# UD27C.net
KiCad netlist of a schematic drawn in EAGLE
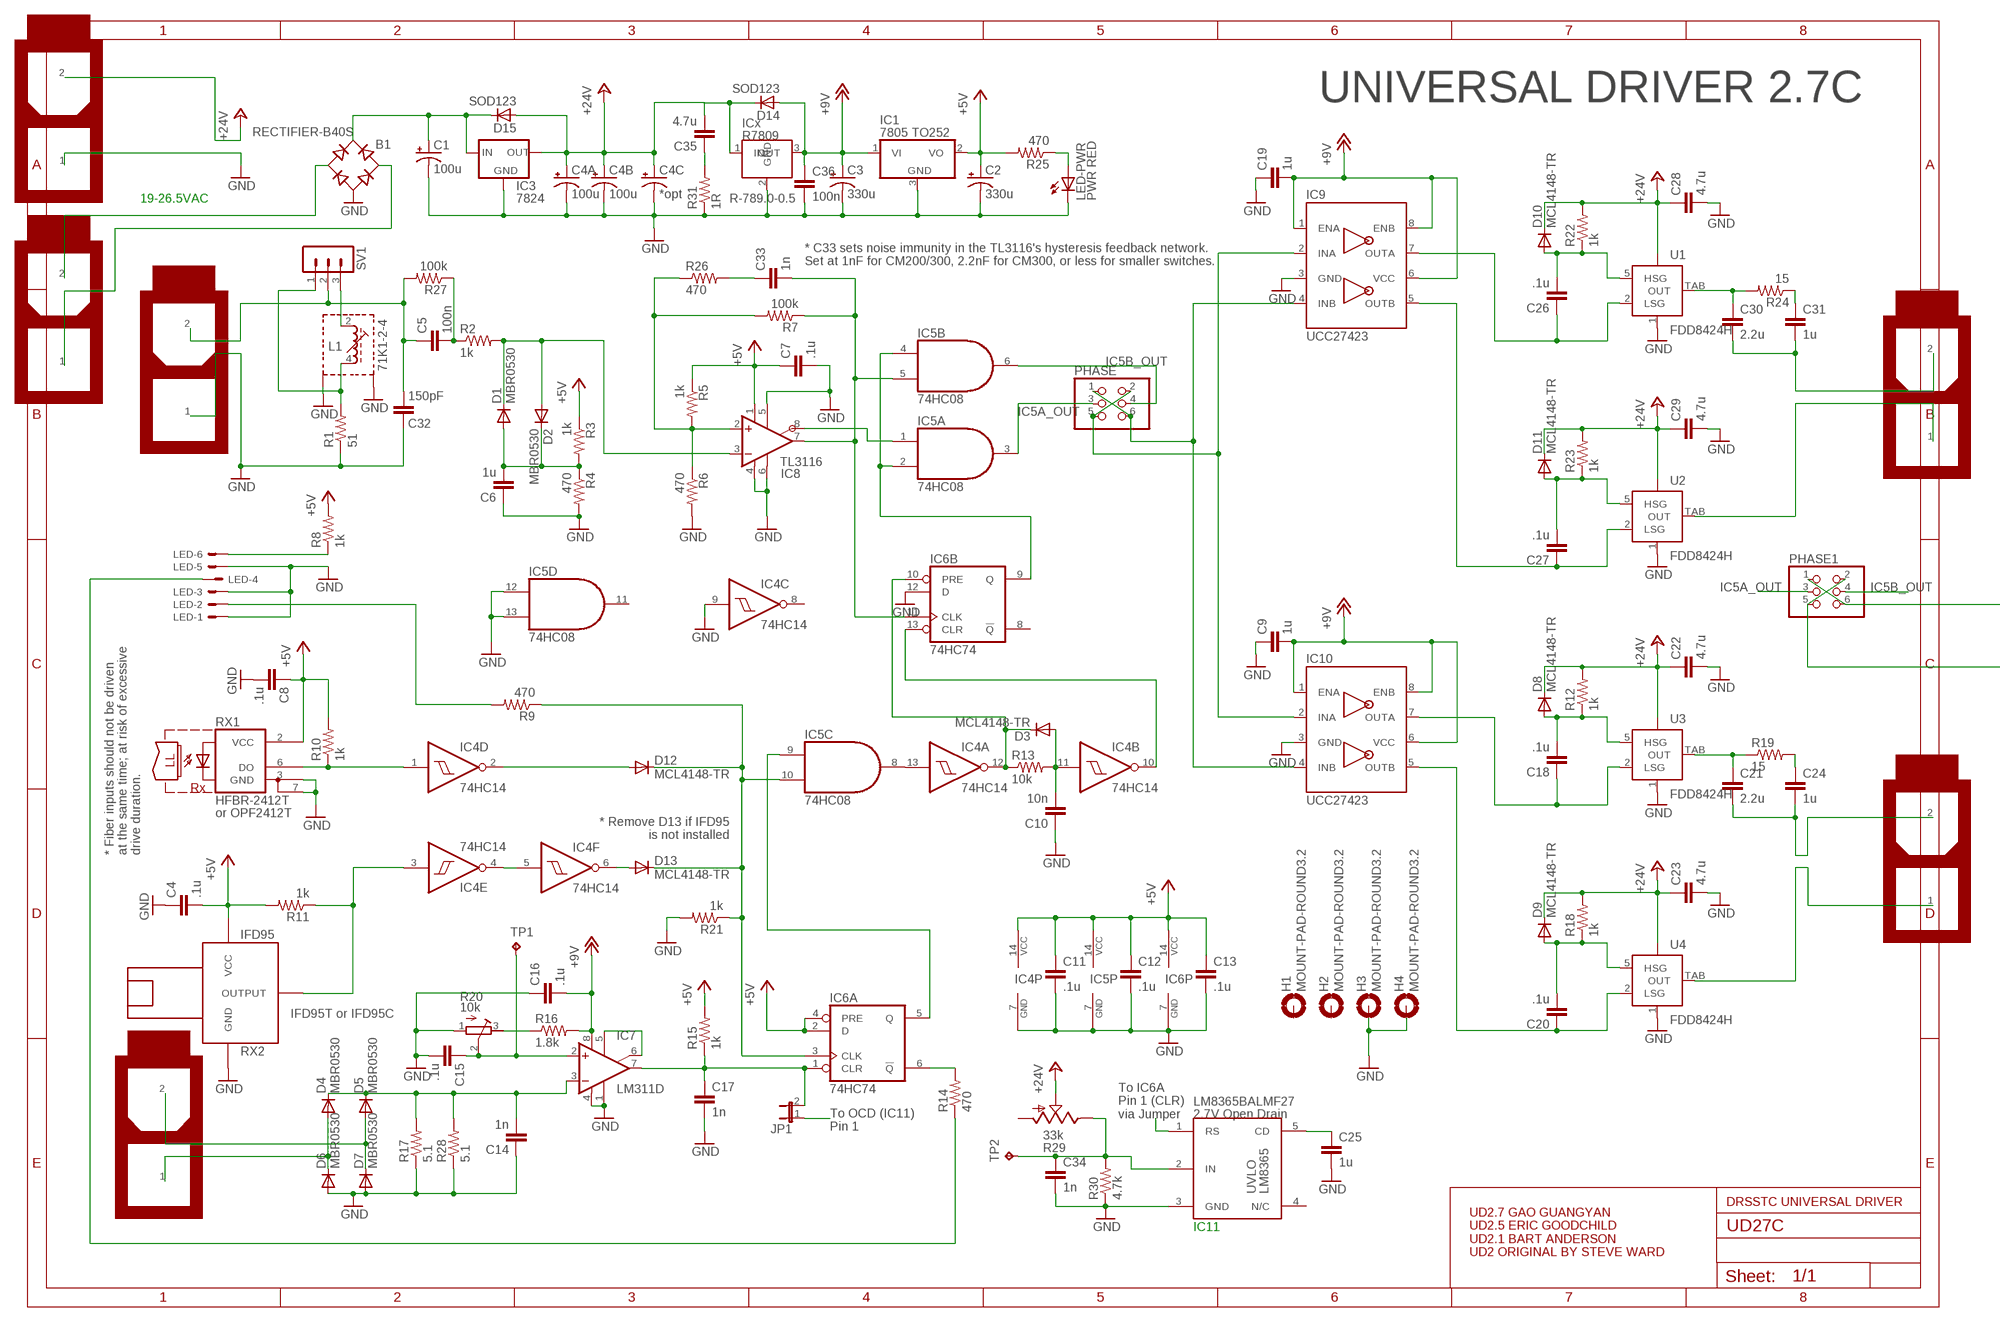
[diagram p0: schematic, sheet 1, part 1 of 2]
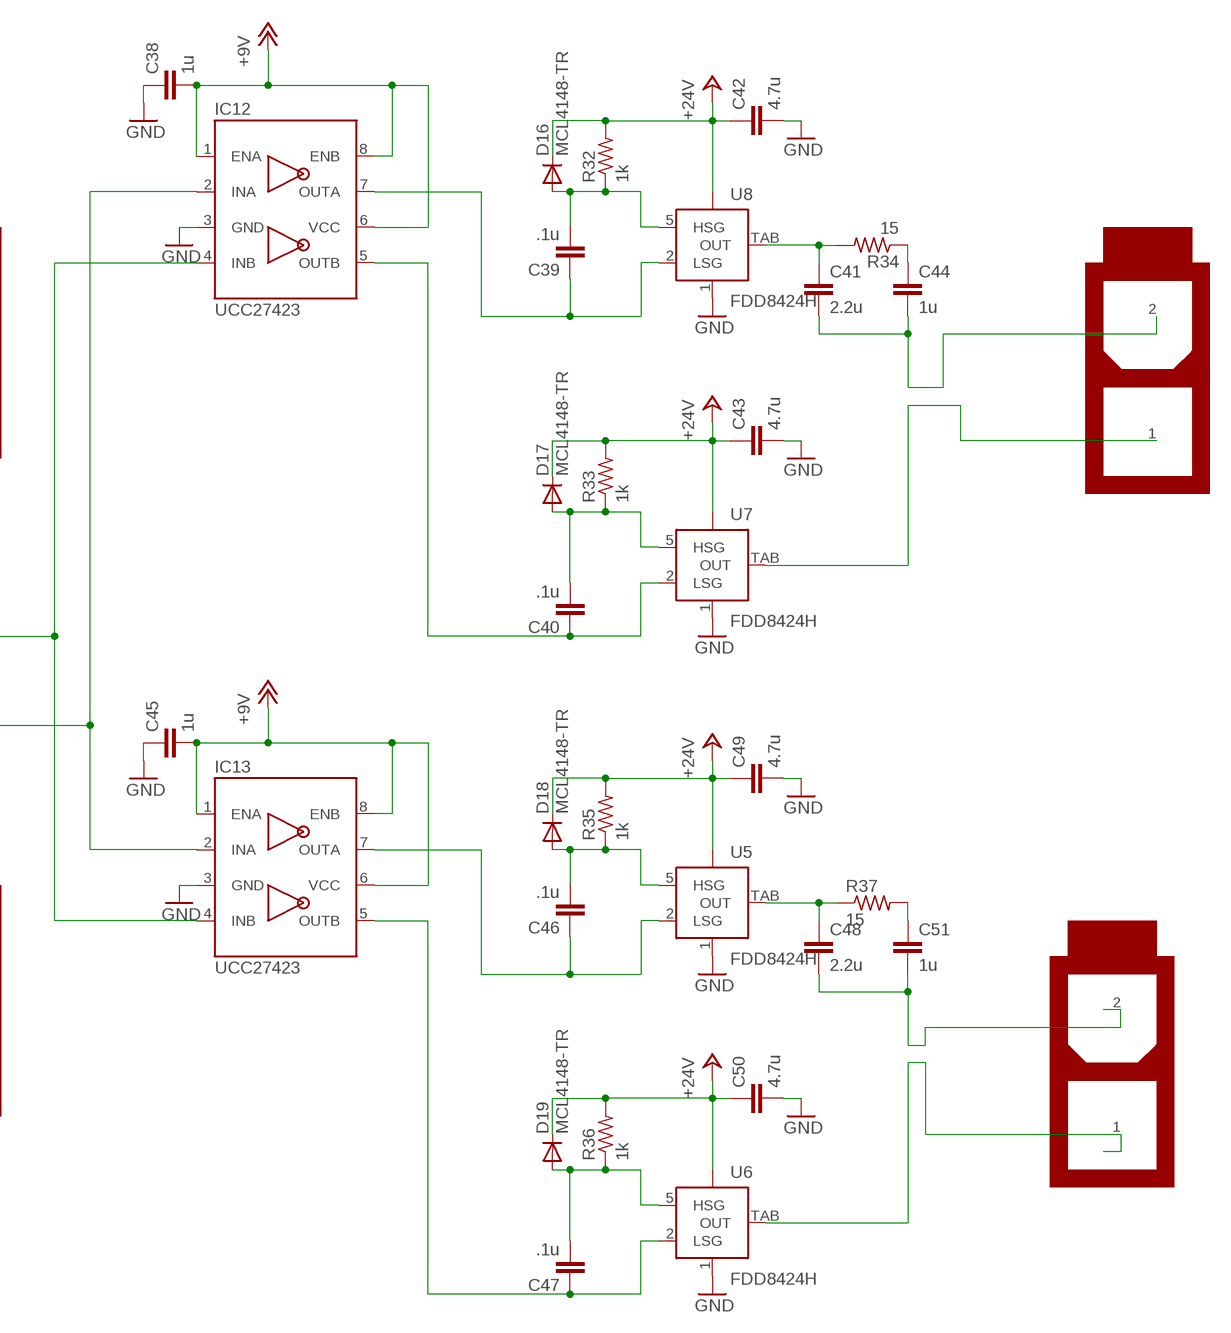
[diagram p1: schematic, sheet 1, part 2 of 2]

(export (version "E")
  (design (tool "Eeschema 10.0.6"))
  (components
    (comp (ref "B1")
      (value "RECTIFIER-B40S")
      (footprint "eagle-import:B40S")
      (libsource (lib "eagle-import") (part "RECTIFIER-B40S"))
    )
    (comp (ref "C1")
      (value "100u")
      (footprint "eagle-import:E3,5-8")
      (libsource (lib "eagle-import") (part "CPOL-USE3.5-8"))
    )
    (comp (ref "C2")
      (value "330u")
      (footprint "eagle-import:E3,5-8")
      (libsource (lib "eagle-import") (part "CPOL-USE3.5-8"))
    )
    (comp (ref "C3")
      (value "330u")
      (footprint "eagle-import:E3,5-8")
      (libsource (lib "eagle-import") (part "CPOL-USE3.5-8"))
    )
    (comp (ref "C4")
      (value ".1u")
      (footprint "eagle-import:C0805")
      (libsource (lib "eagle-import") (part "C-EUC0805"))
    )
    (comp (ref "C4A")
      (value "100u")
      (footprint "eagle-import:E3,5-8")
      (libsource (lib "eagle-import") (part "CPOL-USE3.5-8"))
    )
    (comp (ref "C4B")
      (value "100u")
      (footprint "eagle-import:E3,5-8")
      (libsource (lib "eagle-import") (part "CPOL-USE3.5-8"))
    )
    (comp (ref "C4C")
      (value "*opt")
      (footprint "eagle-import:E3,5-8")
      (libsource (lib "eagle-import") (part "CPOL-USE3.5-8"))
    )
    (comp (ref "C5")
      (value "100n")
      (footprint "eagle-import:C0805")
      (libsource (lib "eagle-import") (part "C-EUC0805"))
    )
    (comp (ref "C6")
      (value "1u")
      (footprint "eagle-import:C0805")
      (libsource (lib "eagle-import") (part "C-EUC0805"))
    )
    (comp (ref "C7")
      (value ".1u")
      (footprint "eagle-import:C0805")
      (libsource (lib "eagle-import") (part "C-EUC0805"))
    )
    (comp (ref "C8")
      (value ".1u")
      (footprint "eagle-import:C0805")
      (libsource (lib "eagle-import") (part "C-EUC0805"))
    )
    (comp (ref "C9")
      (value "1u")
      (footprint "eagle-import:C0805")
      (libsource (lib "eagle-import") (part "C-EUC0805"))
    )
    (comp (ref "C10")
      (value "10n")
      (footprint "eagle-import:C0805")
      (libsource (lib "eagle-import") (part "C-EUC0805"))
    )
    (comp (ref "C11")
      (value ".1u")
      (footprint "eagle-import:C0805")
      (libsource (lib "eagle-import") (part "C-EUC0805"))
    )
    (comp (ref "C12")
      (value ".1u")
      (footprint "eagle-import:C0805")
      (libsource (lib "eagle-import") (part "C-EUC0805"))
    )
    (comp (ref "C13")
      (value ".1u")
      (footprint "eagle-import:C0805")
      (libsource (lib "eagle-import") (part "C-EUC0805"))
    )
    (comp (ref "C14")
      (value "1n")
      (footprint "eagle-import:C0805")
      (libsource (lib "eagle-import") (part "C-EUC0805"))
    )
    (comp (ref "C15")
      (value ".1u")
      (footprint "eagle-import:C0805")
      (libsource (lib "eagle-import") (part "C-EUC0805"))
    )
    (comp (ref "C16")
      (value ".1u")
      (footprint "eagle-import:C0805")
      (libsource (lib "eagle-import") (part "C-EUC0805"))
    )
    (comp (ref "C17")
      (value "1n")
      (footprint "eagle-import:C0805")
      (libsource (lib "eagle-import") (part "C-EUC0805"))
    )
    (comp (ref "C18")
      (value ".1u")
      (footprint "eagle-import:C0805")
      (libsource (lib "eagle-import") (part "C-EUC0805"))
    )
    (comp (ref "C19")
      (value "1u")
      (footprint "eagle-import:C0805")
      (libsource (lib "eagle-import") (part "C-EUC0805"))
    )
    (comp (ref "C20")
      (value ".1u")
      (footprint "eagle-import:C0805")
      (libsource (lib "eagle-import") (part "C-EUC0805"))
    )
    (comp (ref "C21")
      (value "2.2u")
      (footprint "eagle-import:C1210")
      (libsource (lib "eagle-import") (part "C-EUC1210"))
    )
    (comp (ref "C22")
      (value "4.7u")
      (footprint "eagle-import:C1206")
      (libsource (lib "eagle-import") (part "C-EUC1206"))
    )
    (comp (ref "C23")
      (value "4.7u")
      (footprint "eagle-import:C1206")
      (libsource (lib "eagle-import") (part "C-EUC1206"))
    )
    (comp (ref "C24")
      (value "1u")
      (footprint "eagle-import:C1206")
      (libsource (lib "eagle-import") (part "C-EUC1206"))
    )
    (comp (ref "C25")
      (value "1u")
      (footprint "eagle-import:C0805")
      (libsource (lib "eagle-import") (part "C-EUC0805"))
    )
    (comp (ref "C26")
      (value ".1u")
      (footprint "eagle-import:C0805")
      (libsource (lib "eagle-import") (part "C-EUC0805"))
    )
    (comp (ref "C27")
      (value ".1u")
      (footprint "eagle-import:C0805")
      (libsource (lib "eagle-import") (part "C-EUC0805"))
    )
    (comp (ref "C28")
      (value "4.7u")
      (footprint "eagle-import:C1206")
      (libsource (lib "eagle-import") (part "C-EUC1206"))
    )
    (comp (ref "C29")
      (value "4.7u")
      (footprint "eagle-import:C1206")
      (libsource (lib "eagle-import") (part "C-EUC1206"))
    )
    (comp (ref "C30")
      (value "2.2u")
      (footprint "eagle-import:C1210")
      (libsource (lib "eagle-import") (part "C-EUC1210"))
    )
    (comp (ref "C31")
      (value "1u")
      (footprint "eagle-import:C1206")
      (libsource (lib "eagle-import") (part "C-EUC1206"))
    )
    (comp (ref "C32")
      (value "150pF")
      (footprint "eagle-import:C0805")
      (libsource (lib "eagle-import") (part "C-EUC0805"))
    )
    (comp (ref "C33")
      (value "1n")
      (footprint "eagle-import:C1206")
      (libsource (lib "eagle-import") (part "C-EUC1206"))
    )
    (comp (ref "C34")
      (value "1n")
      (footprint "eagle-import:C0805")
      (libsource (lib "eagle-import") (part "C-EUC0805"))
    )
    (comp (ref "C35")
      (value "4.7u")
      (footprint "eagle-import:C1206K")
      (libsource (lib "eagle-import") (part "C-EUC1206K"))
    )
    (comp (ref "C36")
      (value "100n")
      (footprint "eagle-import:C0805")
      (libsource (lib "eagle-import") (part "C-EUC0805"))
    )
    (comp (ref "C38")
      (value "1u")
      (footprint "eagle-import:C0805")
      (libsource (lib "eagle-import") (part "C-EUC0805"))
    )
    (comp (ref "C39")
      (value ".1u")
      (footprint "eagle-import:C0805")
      (libsource (lib "eagle-import") (part "C-EUC0805"))
    )
    (comp (ref "C40")
      (value ".1u")
      (footprint "eagle-import:C0805")
      (libsource (lib "eagle-import") (part "C-EUC0805"))
    )
    (comp (ref "C41")
      (value "2.2u")
      (footprint "eagle-import:C1210")
      (libsource (lib "eagle-import") (part "C-EUC1210"))
    )
    (comp (ref "C42")
      (value "4.7u")
      (footprint "eagle-import:C1206")
      (libsource (lib "eagle-import") (part "C-EUC1206"))
    )
    (comp (ref "C43")
      (value "4.7u")
      (footprint "eagle-import:C1206")
      (libsource (lib "eagle-import") (part "C-EUC1206"))
    )
    (comp (ref "C44")
      (value "1u")
      (footprint "eagle-import:C1206")
      (libsource (lib "eagle-import") (part "C-EUC1206"))
    )
    (comp (ref "C45")
      (value "1u")
      (footprint "eagle-import:C0805")
      (libsource (lib "eagle-import") (part "C-EUC0805"))
    )
    (comp (ref "C46")
      (value ".1u")
      (footprint "eagle-import:C0805")
      (libsource (lib "eagle-import") (part "C-EUC0805"))
    )
    (comp (ref "C47")
      (value ".1u")
      (footprint "eagle-import:C0805")
      (libsource (lib "eagle-import") (part "C-EUC0805"))
    )
    (comp (ref "C48")
      (value "2.2u")
      (footprint "eagle-import:C1210")
      (libsource (lib "eagle-import") (part "C-EUC1210"))
    )
    (comp (ref "C49")
      (value "4.7u")
      (footprint "eagle-import:C1206")
      (libsource (lib "eagle-import") (part "C-EUC1206"))
    )
    (comp (ref "C50")
      (value "4.7u")
      (footprint "eagle-import:C1206")
      (libsource (lib "eagle-import") (part "C-EUC1206"))
    )
    (comp (ref "C51")
      (value "1u")
      (footprint "eagle-import:C1206")
      (libsource (lib "eagle-import") (part "C-EUC1206"))
    )
    (comp (ref "D1")
      (value "MBR0530")
      (footprint "eagle-import:SOD323-W")
      (libsource (lib "eagle-import") (part "1N4148"))
    )
    (comp (ref "D2")
      (value "MBR0530")
      (footprint "eagle-import:SOD323-W")
      (libsource (lib "eagle-import") (part "1N4148"))
    )
    (comp (ref "D3")
      (value "MCL4148-TR")
      (footprint "eagle-import:SOD323-W")
      (libsource (lib "eagle-import") (part "1N4148"))
    )
    (comp (ref "D4")
      (value "MBR0530")
      (footprint "eagle-import:SOD323-W")
      (libsource (lib "eagle-import") (part "1N4148"))
    )
    (comp (ref "D5")
      (value "MBR0530")
      (footprint "eagle-import:SOD323-W")
      (libsource (lib "eagle-import") (part "1N4148"))
    )
    (comp (ref "D6")
      (value "MBR0530")
      (footprint "eagle-import:SOD323-W")
      (libsource (lib "eagle-import") (part "1N4148"))
    )
    (comp (ref "D7")
      (value "MBR0530")
      (footprint "eagle-import:SOD323-W")
      (libsource (lib "eagle-import") (part "1N4148"))
    )
    (comp (ref "D8")
      (value "MCL4148-TR")
      (footprint "eagle-import:SOD323-W")
      (libsource (lib "eagle-import") (part "1N4148"))
    )
    (comp (ref "D9")
      (value "MCL4148-TR")
      (footprint "eagle-import:SOD323-W")
      (libsource (lib "eagle-import") (part "1N4148"))
    )
    (comp (ref "D10")
      (value "MCL4148-TR")
      (footprint "eagle-import:SOD323-W")
      (libsource (lib "eagle-import") (part "1N4148"))
    )
    (comp (ref "D11")
      (value "MCL4148-TR")
      (footprint "eagle-import:SOD323-W")
      (libsource (lib "eagle-import") (part "1N4148"))
    )
    (comp (ref "D12")
      (value "MCL4148-TR")
      (footprint "eagle-import:SOD323-W")
      (libsource (lib "eagle-import") (part "1N4148"))
    )
    (comp (ref "D13")
      (value "MCL4148-TR")
      (footprint "eagle-import:SOD323-W")
      (libsource (lib "eagle-import") (part "1N4148"))
    )
    (comp (ref "D14")
      (value "SOD123")
      (footprint "eagle-import:SOD123")
      (libsource (lib "eagle-import") (part "D-SOD123"))
    )
    (comp (ref "D15")
      (value "SOD123")
      (footprint "eagle-import:SOD123")
      (libsource (lib "eagle-import") (part "D-SOD123"))
    )
    (comp (ref "D16")
      (value "MCL4148-TR")
      (footprint "eagle-import:SOD323-W")
      (libsource (lib "eagle-import") (part "1N4148"))
    )
    (comp (ref "D17")
      (value "MCL4148-TR")
      (footprint "eagle-import:SOD323-W")
      (libsource (lib "eagle-import") (part "1N4148"))
    )
    (comp (ref "D18")
      (value "MCL4148-TR")
      (footprint "eagle-import:SOD323-W")
      (libsource (lib "eagle-import") (part "1N4148"))
    )
    (comp (ref "D19")
      (value "MCL4148-TR")
      (footprint "eagle-import:SOD323-W")
      (libsource (lib "eagle-import") (part "1N4148"))
    )
    (comp (ref "H1")
      (value "MOUNT-PAD-ROUND3.2")
      (footprint "eagle-import:3,2-PAD")
      (libsource (lib "eagle-import") (part "MOUNT-PAD-ROUND3.2"))
    )
    (comp (ref "H2")
      (value "MOUNT-PAD-ROUND3.2")
      (footprint "eagle-import:3,2-PAD")
      (libsource (lib "eagle-import") (part "MOUNT-PAD-ROUND3.2"))
    )
    (comp (ref "H3")
      (value "MOUNT-PAD-ROUND3.2")
      (footprint "eagle-import:3,2-PAD")
      (libsource (lib "eagle-import") (part "MOUNT-PAD-ROUND3.2"))
    )
    (comp (ref "H4")
      (value "MOUNT-PAD-ROUND3.2")
      (footprint "eagle-import:3,2-PAD")
      (libsource (lib "eagle-import") (part "MOUNT-PAD-ROUND3.2"))
    )
    (comp (ref "IC1")
      (value "7805 TO252")
      (footprint "eagle-import:TO252")
      (libsource (lib "eagle-import") (part "78DT05"))
    )
    (comp (ref "IC2")
      (value "R78XX")
      (footprint "eagle-import:TO220S")
      (libsource (lib "eagle-import") (part "R78XX"))
    )
    (comp (ref "IC3")
      (value "7824")
      (footprint "eagle-import:D2PACK")
      (libsource (lib "eagle-import") (part "78XXD2PAK"))
    )
    (comp (ref "IC4")
      (value "74HC14")
      (footprint "eagle-import:SO14")
      (libsource (lib "eagle-import") (part "7414D"))
    )
    (comp (ref "IC5")
      (value "74HC08")
      (footprint "eagle-import:SO14")
      (libsource (lib "eagle-import") (part "7408DALS"))
    )
    (comp (ref "IC6")
      (value "74HC74")
      (footprint "eagle-import:SO14")
      (libsource (lib "eagle-import") (part "7474DLS"))
    )
    (comp (ref "IC7")
      (value "LM311D")
      (footprint "eagle-import:SO08")
      (libsource (lib "eagle-import") (part "LM311D"))
    )
    (comp (ref "IC8")
      (value "TL3116")
      (footprint "eagle-import:SO08")
      (libsource (lib "eagle-import") (part "TL3116"))
    )
    (comp (ref "IC9")
      (value "UCC27423")
      (footprint "eagle-import:SO08")
      (libsource (lib "eagle-import") (part "UCC27423"))
    )
    (comp (ref "IC10")
      (value "UCC27423")
      (footprint "eagle-import:SO08")
      (libsource (lib "eagle-import") (part "UCC27423"))
    )
    (comp (ref "IC11")
      (value "LM8365")
      (footprint "eagle-import:SOT25")
      (libsource (lib "eagle-import") (part "LM8365"))
    )
    (comp (ref "IC12")
      (value "UCC27423")
      (footprint "eagle-import:SO08")
      (libsource (lib "eagle-import") (part "UCC27423"))
    )
    (comp (ref "IC13")
      (value "UCC27423")
      (footprint "eagle-import:SO08")
      (libsource (lib "eagle-import") (part "UCC27423"))
    )
    (comp (ref "JP1")
      (value "JP1E")
      (footprint "eagle-import:JP1")
      (libsource (lib "eagle-import") (part "JP1E"))
    )
    (comp (ref "L1")
      (value "71K1-2-4")
      (footprint "eagle-import:71K")
      (libsource (lib "eagle-import") (part "71K1-2-4"))
    )
    (comp (ref "LED")
      (value "22-23-2061")
      (footprint "eagle-import:22-23-2061")
      (fields (field (name "MF") "MOLEX"))
      (libsource (lib "eagle-import") (part "22-23-2061"))
    )
    (comp (ref "LED-PWR")
      (value "PWR RED")
      (footprint "eagle-import:CHIP-LED0805")
      (libsource (lib "eagle-import") (part "LEDCHIP-LED0805"))
    )
    (comp (ref "PHASE")
      (value "PINHD-2X3")
      (footprint "eagle-import:2X03")
      (libsource (lib "eagle-import") (part "PINHD-2X3"))
    )
    (comp (ref "PHASE1")
      (value "PINHD-2X3")
      (footprint "eagle-import:2X03")
      (libsource (lib "eagle-import") (part "PINHD-2X3"))
    )
    (comp (ref "R1")
      (value "51")
      (footprint "eagle-import:0411_15")
      (libsource (lib "eagle-import") (part "R-US_0411/15"))
    )
    (comp (ref "R2")
      (value "1k")
      (footprint "eagle-import:M0805")
      (libsource (lib "eagle-import") (part "R-US_M0805"))
    )
    (comp (ref "R3")
      (value "1k")
      (footprint "eagle-import:M0805")
      (libsource (lib "eagle-import") (part "R-US_M0805"))
    )
    (comp (ref "R4")
      (value "470")
      (footprint "eagle-import:M0805")
      (libsource (lib "eagle-import") (part "R-US_M0805"))
    )
    (comp (ref "R5")
      (value "1k")
      (footprint "eagle-import:M0805")
      (libsource (lib "eagle-import") (part "R-US_M0805"))
    )
    (comp (ref "R6")
      (value "470")
      (footprint "eagle-import:M0805")
      (libsource (lib "eagle-import") (part "R-US_M0805"))
    )
    (comp (ref "R7")
      (value "100k")
      (footprint "eagle-import:M0805")
      (libsource (lib "eagle-import") (part "R-US_M0805"))
    )
    (comp (ref "R8")
      (value "1k")
      (footprint "eagle-import:R0805")
      (libsource (lib "eagle-import") (part "R-US_R0805"))
    )
    (comp (ref "R9")
      (value "470")
      (footprint "eagle-import:R0805")
      (libsource (lib "eagle-import") (part "R-US_R0805"))
    )
    (comp (ref "R10")
      (value "1k")
      (footprint "eagle-import:R0805")
      (libsource (lib "eagle-import") (part "R-US_R0805"))
    )
    (comp (ref "R11")
      (value "1k")
      (footprint "eagle-import:R0805")
      (libsource (lib "eagle-import") (part "R-US_R0805"))
    )
    (comp (ref "R12")
      (value "1k")
      (footprint "eagle-import:M0805")
      (libsource (lib "eagle-import") (part "R-US_M0805"))
    )
    (comp (ref "R13")
      (value "10k")
      (footprint "eagle-import:R0805")
      (libsource (lib "eagle-import") (part "R-US_R0805"))
    )
    (comp (ref "R14")
      (value "470")
      (footprint "eagle-import:R0805")
      (libsource (lib "eagle-import") (part "R-US_R0805"))
    )
    (comp (ref "R15")
      (value "1k")
      (footprint "eagle-import:R0805")
      (libsource (lib "eagle-import") (part "R-US_R0805"))
    )
    (comp (ref "R16")
      (value "1.8k")
      (footprint "eagle-import:R0805")
      (libsource (lib "eagle-import") (part "R-US_R0805"))
    )
    (comp (ref "R17")
      (value "5.1")
      (footprint "eagle-import:0309_12")
      (libsource (lib "eagle-import") (part "R-US_0309/12"))
    )
    (comp (ref "R18")
      (value "1k")
      (footprint "eagle-import:R0805")
      (libsource (lib "eagle-import") (part "R-US_R0805"))
    )
    (comp (ref "R19")
      (value "15")
      (footprint "eagle-import:R1210W")
      (libsource (lib "eagle-import") (part "R-US_R1210W"))
    )
    (comp (ref "R20")
      (value "10k")
      (footprint "eagle-import:RTRIM3296W")
      (libsource (lib "eagle-import") (part "R-TRIMM3296W"))
    )
    (comp (ref "R21")
      (value "1k")
      (footprint "eagle-import:R0805")
      (libsource (lib "eagle-import") (part "R-US_R0805"))
    )
    (comp (ref "R22")
      (value "1k")
      (footprint "eagle-import:M0805")
      (libsource (lib "eagle-import") (part "R-US_M0805"))
    )
    (comp (ref "R23")
      (value "1k")
      (footprint "eagle-import:R0805")
      (libsource (lib "eagle-import") (part "R-US_R0805"))
    )
    (comp (ref "R24")
      (value "15")
      (footprint "eagle-import:R1210W")
      (libsource (lib "eagle-import") (part "R-US_R1210W"))
    )
    (comp (ref "R25")
      (value "470")
      (footprint "eagle-import:M0805")
      (libsource (lib "eagle-import") (part "R-US_M0805"))
    )
    (comp (ref "R26")
      (value "470")
      (footprint "eagle-import:M0805")
      (libsource (lib "eagle-import") (part "R-US_M0805"))
    )
    (comp (ref "R27")
      (value "100k")
      (footprint "eagle-import:M0805")
      (libsource (lib "eagle-import") (part "R-US_M0805"))
    )
    (comp (ref "R28")
      (value "5.1")
      (footprint "eagle-import:0309_12")
      (libsource (lib "eagle-import") (part "R-US_0309/12"))
    )
    (comp (ref "R29")
      (value "33k")
      (footprint "eagle-import:3223J")
      (libsource (lib "eagle-import") (part "TRIM_US-3223J"))
    )
    (comp (ref "R30")
      (value "4.7k")
      (footprint "eagle-import:R0805")
      (libsource (lib "eagle-import") (part "R-US_R0805"))
    )
    (comp (ref "R31")
      (value "1R")
      (footprint "eagle-import:M0805")
      (libsource (lib "eagle-import") (part "R-US_M0805"))
    )
    (comp (ref "R32")
      (value "1k")
      (footprint "eagle-import:M0805")
      (libsource (lib "eagle-import") (part "R-US_M0805"))
    )
    (comp (ref "R33")
      (value "1k")
      (footprint "eagle-import:R0805")
      (libsource (lib "eagle-import") (part "R-US_R0805"))
    )
    (comp (ref "R34")
      (value "15")
      (footprint "eagle-import:R1210W")
      (libsource (lib "eagle-import") (part "R-US_R1210W"))
    )
    (comp (ref "R35")
      (value "1k")
      (footprint "eagle-import:M0805")
      (libsource (lib "eagle-import") (part "R-US_M0805"))
    )
    (comp (ref "R36")
      (value "1k")
      (footprint "eagle-import:R0805")
      (libsource (lib "eagle-import") (part "R-US_R0805"))
    )
    (comp (ref "R37")
      (value "15")
      (footprint "eagle-import:R1210W")
      (libsource (lib "eagle-import") (part "R-US_R1210W"))
    )
    (comp (ref "RX1")
      (value "HFBR-2412T")
      (footprint "eagle-import:HFBR-X41XT")
      (fields (field (name "MF") "AGILENT TECHNOLOGIES"))
      (libsource (lib "eagle-import") (part "HFBR-2412T"))
    )
    (comp (ref "RX2")
      (value "IFD95")
      (footprint "eagle-import:OPTO-RECEIVER")
      (libsource (lib "eagle-import") (part "IFD95"))
    )
    (comp (ref "SV1")
      (value "MA03-1")
      (footprint "eagle-import:MA03-1")
      (libsource (lib "eagle-import") (part "MA03-1"))
    )
    (comp (ref "TP1")
      (value "TPTP16R")
      (footprint "eagle-import:TP16R")
      (libsource (lib "eagle-import") (part "TPTP16R"))
    )
    (comp (ref "TP2")
      (value "TPB1,27")
      (footprint "eagle-import:B1,27")
      (libsource (lib "eagle-import") (part "TPB1,27"))
    )
    (comp (ref "U$1")
      (value "5566-2NP")
      (footprint "eagle-import:5566-2NP")
      (libsource (lib "eagle-import") (part "5566-2NP"))
    )
    (comp (ref "U$2")
      (value "5566-2NP")
      (footprint "eagle-import:5566-2NP")
      (libsource (lib "eagle-import") (part "5566-2NP"))
    )
    (comp (ref "U$3")
      (value "5566-2NP")
      (footprint "eagle-import:5566-2NP")
      (libsource (lib "eagle-import") (part "5566-2NP"))
    )
    (comp (ref "U$4")
      (value "5566-2NP")
      (footprint "eagle-import:5566-2NP")
      (libsource (lib "eagle-import") (part "5566-2NP"))
    )
    (comp (ref "U$5")
      (value "5566-2NP")
      (footprint "eagle-import:5566-2NP")
      (libsource (lib "eagle-import") (part "5566-2NP"))
    )
    (comp (ref "U$6")
      (value "5566-2NP")
      (footprint "eagle-import:5566-2NP")
      (libsource (lib "eagle-import") (part "5566-2NP"))
    )
    (comp (ref "U$7")
      (value "5566-2NP")
      (footprint "eagle-import:5566-2NP")
      (libsource (lib "eagle-import") (part "5566-2NP"))
    )
    (comp (ref "U$8")
      (value "5566-2NP")
      (footprint "eagle-import:5566-2NP")
      (libsource (lib "eagle-import") (part "5566-2NP"))
    )
    (comp (ref "U1")
      (value "FDD8424H")
      (footprint "eagle-import:GGY_TO252_5")
      (libsource (lib "eagle-import") (part "GGY_FDD8424H"))
    )
    (comp (ref "U2")
      (value "FDD8424H")
      (footprint "eagle-import:GGY_TO252_5")
      (libsource (lib "eagle-import") (part "GGY_FDD8424H"))
    )
    (comp (ref "U3")
      (value "FDD8424H")
      (footprint "eagle-import:GGY_TO252_5")
      (libsource (lib "eagle-import") (part "GGY_FDD8424H"))
    )
    (comp (ref "U4")
      (value "FDD8424H")
      (footprint "eagle-import:GGY_TO252_5")
      (libsource (lib "eagle-import") (part "GGY_FDD8424H"))
    )
    (comp (ref "U5")
      (value "FDD8424H")
      (footprint "eagle-import:GGY_TO252_5")
      (libsource (lib "eagle-import") (part "GGY_FDD8424H"))
    )
    (comp (ref "U6")
      (value "FDD8424H")
      (footprint "eagle-import:GGY_TO252_5")
      (libsource (lib "eagle-import") (part "GGY_FDD8424H"))
    )
    (comp (ref "U7")
      (value "FDD8424H")
      (footprint "eagle-import:GGY_TO252_5")
      (libsource (lib "eagle-import") (part "GGY_FDD8424H"))
    )
    (comp (ref "U8")
      (value "FDD8424H")
      (footprint "eagle-import:GGY_TO252_5")
      (libsource (lib "eagle-import") (part "GGY_FDD8424H"))
    )
  )
  (nets
    (net (code "1") (name "+5V") (class "Default")
      (node (ref "C11") (pin "1") (pinfunction "1_1") (pintype "passive"))
      (node (ref "C12") (pin "1") (pinfunction "1_1") (pintype "passive"))
      (node (ref "C13") (pin "1") (pinfunction "1_1") (pintype "passive"))
      (node (ref "C2") (pin "+") (pinfunction "+_+") (pintype "passive"))
      (node (ref "C4") (pin "2") (pinfunction "2_2") (pintype "passive"))
      (node (ref "C7") (pin "1") (pinfunction "1_1") (pintype "passive"))
      (node (ref "C8") (pin "1") (pinfunction "1_1") (pintype "passive"))
      (node (ref "IC1") (pin "2") (pinfunction "VO_2") (pintype "passive"))
      (node (ref "IC4") (pin "14") (pinfunction "VCC_14") (pintype "power_in"))
      (node (ref "IC5") (pin "14") (pinfunction "VCC_14") (pintype "power_in"))
      (node (ref "IC6") (pin "14") (pinfunction "VCC_14") (pintype "power_in"))
      (node (ref "IC6") (pin "2") (pinfunction "D_2") (pintype "input"))
      (node (ref "IC6") (pin "4") (pinfunction "PRE_4") (pintype "input"))
      (node (ref "IC8") (pin "1") (pinfunction "V+_1") (pintype "power_in"))
      (node (ref "R10") (pin "2") (pinfunction "2_2") (pintype "passive"))
      (node (ref "R11") (pin "2") (pinfunction "2_2") (pintype "passive"))
      (node (ref "R15") (pin "2") (pinfunction "2_2") (pintype "passive"))
      (node (ref "R25") (pin "2") (pinfunction "2_2") (pintype "passive"))
      (node (ref "R3") (pin "1") (pinfunction "1_1") (pintype "passive"))
      (node (ref "R5") (pin "1") (pinfunction "1_1") (pintype "passive"))
      (node (ref "R8") (pin "2") (pinfunction "2_2") (pintype "passive"))
      (node (ref "RX1") (pin "2") (pinfunction "VCC_2") (pintype "power_in"))
      (node (ref "RX2") (pin "P$3") (pinfunction "VCC_P$3") (pintype "bidirectional"))
    )
    (net (code "2") (name "+9V") (class "Default")
      (node (ref "C16") (pin "2") (pinfunction "2_2") (pintype "passive"))
      (node (ref "C19") (pin "2") (pinfunction "2_2") (pintype "passive"))
      (node (ref "C3") (pin "+") (pinfunction "+_+") (pintype "passive"))
      (node (ref "C36") (pin "1") (pinfunction "1_1") (pintype "passive"))
      (node (ref "C38") (pin "2") (pinfunction "2_2") (pintype "passive"))
      (node (ref "C45") (pin "2") (pinfunction "2_2") (pintype "passive"))
      (node (ref "C9") (pin "2") (pinfunction "2_2") (pintype "passive"))
      (node (ref "D14") (pin "2") (pinfunction "A_2") (pintype "passive"))
      (node (ref "IC1") (pin "1") (pinfunction "VI_1") (pintype "input"))
      (node (ref "IC10") (pin "1") (pinfunction "ENA_1") (pintype "bidirectional"))
      (node (ref "IC10") (pin "6") (pinfunction "VCC_6") (pintype "bidirectional"))
      (node (ref "IC10") (pin "8") (pinfunction "ENB_8") (pintype "bidirectional"))
      (node (ref "IC12") (pin "1") (pinfunction "ENA_1") (pintype "bidirectional"))
      (node (ref "IC12") (pin "6") (pinfunction "VCC_6") (pintype "bidirectional"))
      (node (ref "IC12") (pin "8") (pinfunction "ENB_8") (pintype "bidirectional"))
      (node (ref "IC13") (pin "1") (pinfunction "ENA_1") (pintype "bidirectional"))
      (node (ref "IC13") (pin "6") (pinfunction "VCC_6") (pintype "bidirectional"))
      (node (ref "IC13") (pin "8") (pinfunction "ENB_8") (pintype "bidirectional"))
      (node (ref "IC2") (pin "3") (pinfunction "OUT_3") (pintype "bidirectional"))
      (node (ref "IC7") (pin "8") (pinfunction "V+_8") (pintype "power_in"))
      (node (ref "IC9") (pin "1") (pinfunction "ENA_1") (pintype "bidirectional"))
      (node (ref "IC9") (pin "6") (pinfunction "VCC_6") (pintype "bidirectional"))
      (node (ref "IC9") (pin "8") (pinfunction "ENB_8") (pintype "bidirectional"))
      (node (ref "R16") (pin "2") (pinfunction "2_2") (pintype "passive"))
    )
    (net (code "3") (name "+24V") (class "Default")
      (node (ref "C22") (pin "1") (pinfunction "1_1") (pintype "passive"))
      (node (ref "C23") (pin "1") (pinfunction "1_1") (pintype "passive"))
      (node (ref "C28") (pin "1") (pinfunction "1_1") (pintype "passive"))
      (node (ref "C29") (pin "1") (pinfunction "1_1") (pintype "passive"))
      (node (ref "C35") (pin "2") (pinfunction "2_2") (pintype "passive"))
      (node (ref "C42") (pin "1") (pinfunction "1_1") (pintype "passive"))
      (node (ref "C43") (pin "1") (pinfunction "1_1") (pintype "passive"))
      (node (ref "C49") (pin "1") (pinfunction "1_1") (pintype "passive"))
      (node (ref "C4A") (pin "+") (pinfunction "+_+") (pintype "passive"))
      (node (ref "C4B") (pin "+") (pinfunction "+_+") (pintype "passive"))
      (node (ref "C4C") (pin "+") (pinfunction "+_+") (pintype "passive"))
      (node (ref "C50") (pin "1") (pinfunction "1_1") (pintype "passive"))
      (node (ref "D10") (pin "C") (pinfunction "C_C") (pintype "passive"))
      (node (ref "D11") (pin "C") (pinfunction "C_C") (pintype "passive"))
      (node (ref "D14") (pin "1") (pinfunction "C_1") (pintype "passive"))
      (node (ref "D15") (pin "2") (pinfunction "A_2") (pintype "passive"))
      (node (ref "D16") (pin "C") (pinfunction "C_C") (pintype "passive"))
      (node (ref "D17") (pin "C") (pinfunction "C_C") (pintype "passive"))
      (node (ref "D18") (pin "C") (pinfunction "C_C") (pintype "passive"))
      (node (ref "D19") (pin "C") (pinfunction "C_C") (pintype "passive"))
      (node (ref "D8") (pin "C") (pinfunction "C_C") (pintype "passive"))
      (node (ref "D9") (pin "C") (pinfunction "C_C") (pintype "passive"))
      (node (ref "IC2") (pin "1") (pinfunction "IN_1") (pintype "bidirectional"))
      (node (ref "IC3") (pin "3") (pinfunction "OUT_3") (pintype "passive"))
      (node (ref "R12") (pin "2") (pinfunction "2_2") (pintype "passive"))
      (node (ref "R18") (pin "2") (pinfunction "2_2") (pintype "passive"))
      (node (ref "R22") (pin "2") (pinfunction "2_2") (pintype "passive"))
      (node (ref "R23") (pin "2") (pinfunction "2_2") (pintype "passive"))
      (node (ref "R29") (pin "2") (pinfunction "S_2") (pintype "passive"))
      (node (ref "R32") (pin "2") (pinfunction "2_2") (pintype "passive"))
      (node (ref "R33") (pin "2") (pinfunction "2_2") (pintype "passive"))
      (node (ref "R35") (pin "2") (pinfunction "2_2") (pintype "passive"))
      (node (ref "R36") (pin "2") (pinfunction "2_2") (pintype "passive"))
      (node (ref "U$1") (pin "2") (pinfunction "PCIE-2_2") (pintype "bidirectional"))
      (node (ref "U1") (pin "4") (pinfunction "VBB_4") (pintype "power_in"))
      (node (ref "U2") (pin "4") (pinfunction "VBB_4") (pintype "power_in"))
      (node (ref "U3") (pin "4") (pinfunction "VBB_4") (pintype "power_in"))
      (node (ref "U4") (pin "4") (pinfunction "VBB_4") (pintype "power_in"))
      (node (ref "U5") (pin "4") (pinfunction "VBB_4") (pintype "power_in"))
      (node (ref "U6") (pin "4") (pinfunction "VBB_4") (pintype "power_in"))
      (node (ref "U7") (pin "4") (pinfunction "VBB_4") (pintype "power_in"))
      (node (ref "U8") (pin "4") (pinfunction "VBB_4") (pintype "power_in"))
    )
    (net (code "4") (name "/IC5A_OUT") (class "Default")
      (node (ref "IC5") (pin "3") (pinfunction "O_3") (pintype "output"))
      (node (ref "PHASE") (pin "3") (pinfunction "3_3") (pintype "passive"))
      (node (ref "PHASE1") (pin "3") (pinfunction "3_3") (pintype "passive"))
    )
    (net (code "5") (name "/IC5B_OUT") (class "Default")
      (node (ref "IC5") (pin "6") (pinfunction "O_6") (pintype "output"))
      (node (ref "PHASE") (pin "4") (pinfunction "4_4") (pintype "passive"))
      (node (ref "PHASE1") (pin "4") (pinfunction "4_4") (pintype "passive"))
    )
    (net (code "6") (name "/N$31") (class "Default")
      (node (ref "IC11") (pin "1") (pinfunction "RS_1") (pintype "bidirectional"))
      (node (ref "JP1") (pin "1") (pinfunction "1_1") (pintype "passive"))
    )
    (net (code "7") (name "GND") (class "Default")
      (node (ref "B1") (pin "-") (pinfunction "-_-") (pintype "passive"))
      (node (ref "C1") (pin "-") (pinfunction "-_-") (pintype "passive"))
      (node (ref "C10") (pin "1") (pinfunction "1_1") (pintype "passive"))
      (node (ref "C11") (pin "2") (pinfunction "2_2") (pintype "passive"))
      (node (ref "C12") (pin "2") (pinfunction "2_2") (pintype "passive"))
      (node (ref "C13") (pin "2") (pinfunction "2_2") (pintype "passive"))
      (node (ref "C14") (pin "1") (pinfunction "1_1") (pintype "passive"))
      (node (ref "C15") (pin "2") (pinfunction "2_2") (pintype "passive"))
      (node (ref "C16") (pin "1") (pinfunction "1_1") (pintype "passive"))
      (node (ref "C17") (pin "2") (pinfunction "2_2") (pintype "passive"))
      (node (ref "C19") (pin "1") (pinfunction "1_1") (pintype "passive"))
      (node (ref "C2") (pin "-") (pinfunction "-_-") (pintype "passive"))
      (node (ref "C22") (pin "2") (pinfunction "2_2") (pintype "passive"))
      (node (ref "C23") (pin "2") (pinfunction "2_2") (pintype "passive"))
      (node (ref "C25") (pin "2") (pinfunction "2_2") (pintype "passive"))
      (node (ref "C28") (pin "2") (pinfunction "2_2") (pintype "passive"))
      (node (ref "C29") (pin "2") (pinfunction "2_2") (pintype "passive"))
      (node (ref "C3") (pin "-") (pinfunction "-_-") (pintype "passive"))
      (node (ref "C32") (pin "1") (pinfunction "1_1") (pintype "passive"))
      (node (ref "C34") (pin "2") (pinfunction "2_2") (pintype "passive"))
      (node (ref "C36") (pin "2") (pinfunction "2_2") (pintype "passive"))
      (node (ref "C38") (pin "1") (pinfunction "1_1") (pintype "passive"))
      (node (ref "C4") (pin "1") (pinfunction "1_1") (pintype "passive"))
      (node (ref "C42") (pin "2") (pinfunction "2_2") (pintype "passive"))
      (node (ref "C43") (pin "2") (pinfunction "2_2") (pintype "passive"))
      (node (ref "C45") (pin "1") (pinfunction "1_1") (pintype "passive"))
      (node (ref "C49") (pin "2") (pinfunction "2_2") (pintype "passive"))
      (node (ref "C4A") (pin "-") (pinfunction "-_-") (pintype "passive"))
      (node (ref "C4B") (pin "-") (pinfunction "-_-") (pintype "passive"))
      (node (ref "C4C") (pin "-") (pinfunction "-_-") (pintype "passive"))
      (node (ref "C50") (pin "2") (pinfunction "2_2") (pintype "passive"))
      (node (ref "C6") (pin "1") (pinfunction "1_1") (pintype "passive"))
      (node (ref "C7") (pin "2") (pinfunction "2_2") (pintype "passive"))
      (node (ref "C8") (pin "2") (pinfunction "2_2") (pintype "passive"))
      (node (ref "C9") (pin "1") (pinfunction "1_1") (pintype "passive"))
      (node (ref "D6") (pin "A") (pinfunction "A_A") (pintype "passive"))
      (node (ref "D7") (pin "A") (pinfunction "A_A") (pintype "passive"))
      (node (ref "H3") (pin "B3,2") (pinfunction "MOUNT_B3,2") (pintype "passive"))
      (node (ref "H4") (pin "B3,2") (pinfunction "MOUNT_B3,2") (pintype "passive"))
      (node (ref "IC1") (pin "3") (pinfunction "GND_3") (pintype "passive"))
      (node (ref "IC10") (pin "3") (pinfunction "GND_3") (pintype "bidirectional"))
      (node (ref "IC11") (pin "3") (pinfunction "GND_3") (pintype "bidirectional"))
      (node (ref "IC12") (pin "3") (pinfunction "GND_3") (pintype "bidirectional"))
      (node (ref "IC13") (pin "3") (pinfunction "GND_3") (pintype "bidirectional"))
      (node (ref "IC2") (pin "2") (pinfunction "GND_2") (pintype "bidirectional"))
      (node (ref "IC3") (pin "2") (pinfunction "GND_2") (pintype "input"))
      (node (ref "IC4") (pin "7") (pinfunction "GND_7") (pintype "power_in"))
      (node (ref "IC4") (pin "9") (pinfunction "I_9") (pintype "input"))
      (node (ref "IC5") (pin "12") (pinfunction "I0_12") (pintype "input"))
      (node (ref "IC5") (pin "13") (pinfunction "I1_13") (pintype "input"))
      (node (ref "IC5") (pin "7") (pinfunction "GND_7") (pintype "power_in"))
      (node (ref "IC6") (pin "12") (pinfunction "D_12") (pintype "input"))
      (node (ref "IC6") (pin "7") (pinfunction "GND_7") (pintype "power_in"))
      (node (ref "IC7") (pin "1") (pinfunction "GND_1") (pintype "passive"))
      (node (ref "IC7") (pin "4") (pinfunction "V-_4") (pintype "power_in"))
      (node (ref "IC8") (pin "4") (pinfunction "V-_4") (pintype "power_in"))
      (node (ref "IC8") (pin "5") (pinfunction "LATCH_5") (pintype "passive"))
      (node (ref "IC8") (pin "6") (pinfunction "GND_6") (pintype "passive"))
      (node (ref "IC9") (pin "3") (pinfunction "GND_3") (pintype "bidirectional"))
      (node (ref "L1") (pin "S1") (pinfunction "S1_S1") (pintype "passive"))
      (node (ref "L1") (pin "S2") (pinfunction "S2_S2") (pintype "passive"))
      (node (ref "LED") (pin "1") (pinfunction "S_1") (pintype "passive"))
      (node (ref "LED") (pin "3") (pinfunction "S_3") (pintype "passive"))
      (node (ref "LED") (pin "5") (pinfunction "S_5") (pintype "passive"))
      (node (ref "LED-PWR") (pin "C") (pinfunction "C_C") (pintype "passive"))
      (node (ref "R1") (pin "1") (pinfunction "1_1") (pintype "passive"))
      (node (ref "R17") (pin "1") (pinfunction "1_1") (pintype "passive"))
      (node (ref "R20") (pin "1") (pinfunction "E_1") (pintype "passive"))
      (node (ref "R21") (pin "2") (pinfunction "2_2") (pintype "passive"))
      (node (ref "R28") (pin "1") (pinfunction "1_1") (pintype "passive"))
      (node (ref "R30") (pin "1") (pinfunction "1_1") (pintype "passive"))
      (node (ref "R31") (pin "1") (pinfunction "1_1") (pintype "passive"))
      (node (ref "R4") (pin "2") (pinfunction "2_2") (pintype "passive"))
      (node (ref "R6") (pin "2") (pinfunction "2_2") (pintype "passive"))
      (node (ref "RX1") (pin "3") (pinfunction "GND_3") (pintype "power_in"))
      (node (ref "RX1") (pin "7") (pinfunction "GND1_7") (pintype "power_in"))
      (node (ref "RX2") (pin "P$1") (pinfunction "GND_P$1") (pintype "bidirectional"))
      (node (ref "U$1") (pin "1") (pinfunction "PCIE-1_1") (pintype "bidirectional"))
      (node (ref "U$7") (pin "1") (pinfunction "PCIE-1_1") (pintype "bidirectional"))
      (node (ref "U1") (pin "1") (pinfunction "GND_1") (pintype "power_in"))
      (node (ref "U2") (pin "1") (pinfunction "GND_1") (pintype "power_in"))
      (node (ref "U3") (pin "1") (pinfunction "GND_1") (pintype "power_in"))
      (node (ref "U4") (pin "1") (pinfunction "GND_1") (pintype "power_in"))
      (node (ref "U5") (pin "1") (pinfunction "GND_1") (pintype "power_in"))
      (node (ref "U6") (pin "1") (pinfunction "GND_1") (pintype "power_in"))
      (node (ref "U7") (pin "1") (pinfunction "GND_1") (pintype "power_in"))
      (node (ref "U8") (pin "1") (pinfunction "GND_1") (pintype "power_in"))
    )
    (net (code "8") (name "Net-(C5-Pad2)") (class "Default")
      (node (ref "C5") (pin "2") (pinfunction "2_2") (pintype "passive"))
      (node (ref "R2") (pin "1") (pinfunction "1_1") (pintype "passive"))
      (node (ref "R27") (pin "1") (pinfunction "1_1") (pintype "passive"))
    )
    (net (code "9") (name "Net-(C6-Pad2)") (class "Default")
      (node (ref "C6") (pin "2") (pinfunction "2_2") (pintype "passive"))
      (node (ref "D1") (pin "A") (pinfunction "A_A") (pintype "passive"))
      (node (ref "D2") (pin "C") (pinfunction "C_C") (pintype "passive"))
      (node (ref "R3") (pin "2") (pinfunction "2_2") (pintype "passive"))
      (node (ref "R4") (pin "1") (pinfunction "1_1") (pintype "passive"))
    )
    (net (code "10") (name "Net-(C24-Pad1)") (class "Default")
      (node (ref "C24") (pin "1") (pinfunction "1_1") (pintype "passive"))
      (node (ref "R19") (pin "2") (pinfunction "2_2") (pintype "passive"))
    )
    (net (code "11") (name "Net-(C31-Pad1)") (class "Default")
      (node (ref "C31") (pin "1") (pinfunction "1_1") (pintype "passive"))
      (node (ref "R24") (pin "1") (pinfunction "1_1") (pintype "passive"))
    )
    (net (code "12") (name "Net-(C33-Pad1)") (class "Default")
      (node (ref "C33") (pin "1") (pinfunction "1_1") (pintype "passive"))
      (node (ref "R26") (pin "2") (pinfunction "2_2") (pintype "passive"))
    )
    (net (code "13") (name "Net-(C35-Pad1)") (class "Default")
      (node (ref "C35") (pin "1") (pinfunction "1_1") (pintype "passive"))
      (node (ref "R31") (pin "2") (pinfunction "2_2") (pintype "passive"))
    )
    (net (code "14") (name "Net-(C44-Pad1)") (class "Default")
      (node (ref "C44") (pin "1") (pinfunction "1_1") (pintype "passive"))
      (node (ref "R34") (pin "1") (pinfunction "1_1") (pintype "passive"))
    )
    (net (code "15") (name "Net-(C51-Pad1)") (class "Default")
      (node (ref "C51") (pin "1") (pinfunction "1_1") (pintype "passive"))
      (node (ref "R37") (pin "2") (pinfunction "2_2") (pintype "passive"))
    )
    (net (code "16") (name "Net-(D15-C)") (class "Default")
      (node (ref "B1") (pin "+") (pinfunction "+_+") (pintype "passive"))
      (node (ref "C1") (pin "+") (pinfunction "+_+") (pintype "passive"))
      (node (ref "D15") (pin "1") (pinfunction "C_1") (pintype "passive"))
      (node (ref "IC3") (pin "1") (pinfunction "IN_1") (pintype "input"))
    )
    (net (code "17") (name "Net-(IC4A-I)") (class "Default")
      (node (ref "IC4") (pin "13") (pinfunction "I_13") (pintype "input"))
      (node (ref "IC5") (pin "8") (pinfunction "O_8") (pintype "output"))
    )
    (net (code "18") (name "Net-(IC4A-O)") (class "Default")
      (node (ref "D3") (pin "C") (pinfunction "C_C") (pintype "passive"))
      (node (ref "IC4") (pin "12") (pinfunction "O_12") (pintype "output"))
      (node (ref "IC6") (pin "10") (pinfunction "PRE_10") (pintype "input"))
      (node (ref "R13") (pin "1") (pinfunction "1_1") (pintype "passive"))
    )
    (net (code "19") (name "Net-(IC4B-I)") (class "Default")
      (node (ref "C10") (pin "2") (pinfunction "2_2") (pintype "passive"))
      (node (ref "D3") (pin "A") (pinfunction "A_A") (pintype "passive"))
      (node (ref "IC4") (pin "11") (pinfunction "I_11") (pintype "input"))
      (node (ref "R13") (pin "2") (pinfunction "2_2") (pintype "passive"))
    )
    (net (code "20") (name "Net-(IC4B-O)") (class "Default")
      (node (ref "IC4") (pin "10") (pinfunction "O_10") (pintype "output"))
      (node (ref "IC6") (pin "13") (pinfunction "CLR_13") (pintype "input"))
    )
    (net (code "21") (name "Net-(IC4D-I)") (class "Default")
      (node (ref "IC4") (pin "1") (pinfunction "I_1") (pintype "input"))
      (node (ref "R10") (pin "1") (pinfunction "1_1") (pintype "passive"))
      (node (ref "RX1") (pin "6") (pinfunction "DO_6") (pintype "passive"))
    )
    (net (code "22") (name "Net-(IC4D-O)") (class "Default")
      (node (ref "D12") (pin "A") (pinfunction "A_A") (pintype "passive"))
      (node (ref "IC4") (pin "2") (pinfunction "O_2") (pintype "output"))
    )
    (net (code "23") (name "Net-(IC4E-I)") (class "Default")
      (node (ref "IC4") (pin "3") (pinfunction "I_3") (pintype "input"))
      (node (ref "R11") (pin "1") (pinfunction "1_1") (pintype "passive"))
      (node (ref "RX2") (pin "P$2") (pinfunction "OUTPUT_P$2") (pintype "bidirectional"))
    )
    (net (code "24") (name "Net-(IC4E-O)") (class "Default")
      (node (ref "IC4") (pin "4") (pinfunction "O_4") (pintype "output"))
      (node (ref "IC4") (pin "5") (pinfunction "I_5") (pintype "input"))
    )
    (net (code "25") (name "Net-(IC4F-O)") (class "Default")
      (node (ref "D13") (pin "A") (pinfunction "A_A") (pintype "passive"))
      (node (ref "IC4") (pin "6") (pinfunction "O_6") (pintype "output"))
    )
    (net (code "26") (name "Net-(IC5A-I0)") (class "Default")
      (node (ref "IC5") (pin "1") (pinfunction "I0_1") (pintype "input"))
      (node (ref "IC8") (pin "8") (pinfunction "QNOT_8") (pintype "output"))
    )
    (net (code "27") (name "Net-(IC5A-I1)") (class "Default")
      (node (ref "IC5") (pin "2") (pinfunction "I1_2") (pintype "input"))
      (node (ref "IC5") (pin "4") (pinfunction "I0_4") (pintype "input"))
      (node (ref "IC6") (pin "9") (pinfunction "Q_9") (pintype "output"))
    )
    (net (code "28") (name "Net-(IC5B-I1)") (class "Default")
      (node (ref "C33") (pin "2") (pinfunction "2_2") (pintype "passive"))
      (node (ref "IC5") (pin "5") (pinfunction "I1_5") (pintype "input"))
      (node (ref "IC6") (pin "11") (pinfunction "CLK_11") (pintype "input"))
      (node (ref "IC8") (pin "7") (pinfunction "Q_7") (pintype "output"))
      (node (ref "R7") (pin "1") (pinfunction "1_1") (pintype "passive"))
    )
    (net (code "29") (name "Net-(IC5C-I0)") (class "Default")
      (node (ref "IC5") (pin "9") (pinfunction "I0_9") (pintype "input"))
      (node (ref "IC6") (pin "5") (pinfunction "Q_5") (pintype "output"))
    )
    (net (code "30") (name "Net-(IC5C-I1)") (class "Default")
      (node (ref "D12") (pin "C") (pinfunction "C_C") (pintype "passive"))
      (node (ref "D13") (pin "C") (pinfunction "C_C") (pintype "passive"))
      (node (ref "IC5") (pin "10") (pinfunction "I1_10") (pintype "input"))
      (node (ref "IC6") (pin "3") (pinfunction "CLK_3") (pintype "input"))
      (node (ref "R21") (pin "1") (pinfunction "1_1") (pintype "passive"))
      (node (ref "R9") (pin "1") (pinfunction "1_1") (pintype "passive"))
    )
    (net (code "31") (name "Net-(IC6A-CLR)") (class "Default")
      (node (ref "C17") (pin "1") (pinfunction "1_1") (pintype "passive"))
      (node (ref "IC6") (pin "1") (pinfunction "CLR_1") (pintype "input"))
      (node (ref "IC7") (pin "7") (pinfunction "OUT_7") (pintype "output"))
      (node (ref "JP1") (pin "2") (pinfunction "2_2") (pintype "passive"))
      (node (ref "R15") (pin "1") (pinfunction "1_1") (pintype "passive"))
    )
    (net (code "32") (name "Net-(IC6A-~{Q})") (class "Default")
      (node (ref "IC6") (pin "6") (pinfunction "~{Q}_6") (pintype "output"))
      (node (ref "R14") (pin "2") (pinfunction "2_2") (pintype "passive"))
    )
    (net (code "33") (name "Net-(IC7-+IN)") (class "Default")
      (node (ref "C15") (pin "1") (pinfunction "1_1") (pintype "passive"))
      (node (ref "IC7") (pin "2") (pinfunction "+IN_2") (pintype "input"))
      (node (ref "R20") (pin "2") (pinfunction "S_2") (pintype "passive"))
      (node (ref "TP1") (pin "TP") (pinfunction "TP_TP") (pintype "input"))
    )
    (net (code "34") (name "Net-(IC7--IN)") (class "Default")
      (node (ref "C14") (pin "2") (pinfunction "2_2") (pintype "passive"))
      (node (ref "D4") (pin "C") (pinfunction "C_C") (pintype "passive"))
      (node (ref "D5") (pin "C") (pinfunction "C_C") (pintype "passive"))
      (node (ref "IC7") (pin "3") (pinfunction "-IN_3") (pintype "input"))
      (node (ref "R17") (pin "2") (pinfunction "2_2") (pintype "passive"))
      (node (ref "R28") (pin "2") (pinfunction "2_2") (pintype "passive"))
    )
    (net (code "35") (name "Net-(IC7-ON)") (class "Default")
      (node (ref "IC7") (pin "5") (pinfunction "ON_5") (pintype "passive"))
      (node (ref "IC7") (pin "6") (pinfunction "ON/STR_6") (pintype "passive"))
    )
    (net (code "36") (name "Net-(IC8-+IN)") (class "Default")
      (node (ref "IC8") (pin "2") (pinfunction "+IN_2") (pintype "input"))
      (node (ref "R26") (pin "1") (pinfunction "1_1") (pintype "passive"))
      (node (ref "R5") (pin "2") (pinfunction "2_2") (pintype "passive"))
      (node (ref "R6") (pin "1") (pinfunction "1_1") (pintype "passive"))
      (node (ref "R7") (pin "2") (pinfunction "2_2") (pintype "passive"))
    )
    (net (code "37") (name "Net-(IC8--IN)") (class "Default")
      (node (ref "D1") (pin "C") (pinfunction "C_C") (pintype "passive"))
      (node (ref "D2") (pin "A") (pinfunction "A_A") (pintype "passive"))
      (node (ref "IC8") (pin "3") (pinfunction "-IN_3") (pintype "input"))
      (node (ref "R2") (pin "2") (pinfunction "2_2") (pintype "passive"))
    )
    (net (code "38") (name "Net-(IC9-OUTA)") (class "Default")
      (node (ref "C26") (pin "1") (pinfunction "1_1") (pintype "passive"))
      (node (ref "IC9") (pin "7") (pinfunction "OUTA_7") (pintype "bidirectional"))
      (node (ref "U1") (pin "2") (pinfunction "LSG_2") (pintype "input"))
    )
    (net (code "39") (name "Net-(IC9-OUTB)") (class "Default")
      (node (ref "C27") (pin "1") (pinfunction "1_1") (pintype "passive"))
      (node (ref "IC9") (pin "5") (pinfunction "OUTB_5") (pintype "bidirectional"))
      (node (ref "U2") (pin "2") (pinfunction "LSG_2") (pintype "input"))
    )
    (net (code "40") (name "Net-(IC10-INA)") (class "Default")
      (node (ref "IC10") (pin "2") (pinfunction "INA_2") (pintype "bidirectional"))
      (node (ref "IC9") (pin "2") (pinfunction "INA_2") (pintype "bidirectional"))
      (node (ref "PHASE") (pin "2") (pinfunction "2_2") (pintype "passive"))
      (node (ref "PHASE") (pin "5") (pinfunction "5_5") (pintype "passive"))
    )
    (net (code "41") (name "Net-(IC10-INB)") (class "Default")
      (node (ref "IC10") (pin "4") (pinfunction "INB_4") (pintype "bidirectional"))
      (node (ref "IC9") (pin "4") (pinfunction "INB_4") (pintype "bidirectional"))
      (node (ref "PHASE") (pin "1") (pinfunction "1_1") (pintype "passive"))
      (node (ref "PHASE") (pin "6") (pinfunction "6_6") (pintype "passive"))
    )
    (net (code "42") (name "Net-(IC10-OUTA)") (class "Default")
      (node (ref "C18") (pin "1") (pinfunction "1_1") (pintype "passive"))
      (node (ref "IC10") (pin "7") (pinfunction "OUTA_7") (pintype "bidirectional"))
      (node (ref "U3") (pin "2") (pinfunction "LSG_2") (pintype "input"))
    )
    (net (code "43") (name "Net-(IC10-OUTB)") (class "Default")
      (node (ref "C20") (pin "1") (pinfunction "1_1") (pintype "passive"))
      (node (ref "IC10") (pin "5") (pinfunction "OUTB_5") (pintype "bidirectional"))
      (node (ref "U4") (pin "2") (pinfunction "LSG_2") (pintype "input"))
    )
    (net (code "44") (name "Net-(IC11-CD)") (class "Default")
      (node (ref "C25") (pin "1") (pinfunction "1_1") (pintype "passive"))
      (node (ref "IC11") (pin "5") (pinfunction "CD_5") (pintype "bidirectional"))
    )
    (net (code "45") (name "Net-(IC11-IN)") (class "Default")
      (node (ref "C34") (pin "1") (pinfunction "1_1") (pintype "passive"))
      (node (ref "IC11") (pin "2") (pinfunction "IN_2") (pintype "bidirectional"))
      (node (ref "R29") (pin "3") (pinfunction "E_3") (pintype "passive"))
      (node (ref "R30") (pin "2") (pinfunction "2_2") (pintype "passive"))
      (node (ref "TP2") (pin "TP") (pinfunction "TP_TP") (pintype "input"))
    )
    (net (code "46") (name "Net-(IC12-INA)") (class "Default")
      (node (ref "IC12") (pin "2") (pinfunction "INA_2") (pintype "bidirectional"))
      (node (ref "IC13") (pin "2") (pinfunction "INA_2") (pintype "bidirectional"))
      (node (ref "PHASE1") (pin "2") (pinfunction "2_2") (pintype "passive"))
      (node (ref "PHASE1") (pin "5") (pinfunction "5_5") (pintype "passive"))
    )
    (net (code "47") (name "Net-(IC12-INB)") (class "Default")
      (node (ref "IC12") (pin "4") (pinfunction "INB_4") (pintype "bidirectional"))
      (node (ref "IC13") (pin "4") (pinfunction "INB_4") (pintype "bidirectional"))
      (node (ref "PHASE1") (pin "1") (pinfunction "1_1") (pintype "passive"))
      (node (ref "PHASE1") (pin "6") (pinfunction "6_6") (pintype "passive"))
    )
    (net (code "48") (name "Net-(IC12-OUTA)") (class "Default")
      (node (ref "C39") (pin "1") (pinfunction "1_1") (pintype "passive"))
      (node (ref "IC12") (pin "7") (pinfunction "OUTA_7") (pintype "bidirectional"))
      (node (ref "U8") (pin "2") (pinfunction "LSG_2") (pintype "input"))
    )
    (net (code "49") (name "Net-(IC12-OUTB)") (class "Default")
      (node (ref "C40") (pin "1") (pinfunction "1_1") (pintype "passive"))
      (node (ref "IC12") (pin "5") (pinfunction "OUTB_5") (pintype "bidirectional"))
      (node (ref "U7") (pin "2") (pinfunction "LSG_2") (pintype "input"))
    )
    (net (code "50") (name "Net-(IC13-OUTA)") (class "Default")
      (node (ref "C46") (pin "1") (pinfunction "1_1") (pintype "passive"))
      (node (ref "IC13") (pin "7") (pinfunction "OUTA_7") (pintype "bidirectional"))
      (node (ref "U5") (pin "2") (pinfunction "LSG_2") (pintype "input"))
    )
    (net (code "51") (name "Net-(IC13-OUTB)") (class "Default")
      (node (ref "C47") (pin "1") (pinfunction "1_1") (pintype "passive"))
      (node (ref "IC13") (pin "5") (pinfunction "OUTB_5") (pintype "bidirectional"))
      (node (ref "U6") (pin "2") (pinfunction "LSG_2") (pintype "input"))
    )
    (net (code "52") (name "Net-(L1A-A)") (class "Default")
      (node (ref "L1") (pin "2") (pinfunction "A_2") (pintype "passive"))
      (node (ref "SV1") (pin "3") (pinfunction "3_3") (pintype "passive"))
    )
    (net (code "53") (name "Net-(L1A-E)") (class "Default")
      (node (ref "L1") (pin "4") (pinfunction "E_4") (pintype "passive"))
      (node (ref "R1") (pin "2") (pinfunction "2_2") (pintype "passive"))
      (node (ref "SV1") (pin "1") (pinfunction "1_1") (pintype "passive"))
    )
    (net (code "54") (name "Net-(LED-PWR-PadA)") (class "Default")
      (node (ref "LED-PWR") (pin "A") (pinfunction "A_A") (pintype "passive"))
      (node (ref "R25") (pin "1") (pinfunction "1_1") (pintype "passive"))
    )
    (net (code "55") (name "Net-(LEDB-S)") (class "Default")
      (node (ref "LED") (pin "2") (pinfunction "S_2") (pintype "passive"))
      (node (ref "R9") (pin "2") (pinfunction "2_2") (pintype "passive"))
    )
    (net (code "56") (name "Net-(LEDD-S)") (class "Default")
      (node (ref "LED") (pin "4") (pinfunction "S_4") (pintype "passive"))
      (node (ref "R14") (pin "1") (pinfunction "1_1") (pintype "passive"))
    )
    (net (code "57") (name "Net-(LEDF-S)") (class "Default")
      (node (ref "LED") (pin "6") (pinfunction "S_6") (pintype "passive"))
      (node (ref "R8") (pin "1") (pinfunction "1_1") (pintype "passive"))
    )
    (net (code "58") (name "Net-(R20-A)") (class "Default")
      (node (ref "R16") (pin "1") (pinfunction "1_1") (pintype "passive"))
      (node (ref "R20") (pin "3") (pinfunction "A_3") (pintype "passive"))
    )
    (net (code "59") (name "Net-(U$2-PCIE-1)") (class "Default")
      (node (ref "B1") (pin "AC2") (pinfunction "AC2_AC2") (pintype "passive"))
      (node (ref "U$2") (pin "1") (pinfunction "PCIE-1_1") (pintype "bidirectional"))
    )
    (net (code "60") (name "Net-(U$2-PCIE-2)") (class "Default")
      (node (ref "B1") (pin "AC1") (pinfunction "AC1_AC1") (pintype "passive"))
      (node (ref "U$2") (pin "2") (pinfunction "PCIE-2_2") (pintype "bidirectional"))
    )
    (net (code "61") (name "Net-(U$3-PCIE-1)") (class "Default")
      (node (ref "U$3") (pin "1") (pinfunction "PCIE-1_1") (pintype "bidirectional"))
      (node (ref "U4") (pin "TAB") (pinfunction "OUT_TAB") (pintype "output"))
    )
    (net (code "62") (name "Net-(U$3-PCIE-2)") (class "Default")
      (node (ref "C21") (pin "2") (pinfunction "2_2") (pintype "passive"))
      (node (ref "C24") (pin "2") (pinfunction "2_2") (pintype "passive"))
      (node (ref "U$3") (pin "2") (pinfunction "PCIE-2_2") (pintype "bidirectional"))
    )
    (net (code "63") (name "Net-(U$4-PCIE-1)") (class "Default")
      (node (ref "U$4") (pin "1") (pinfunction "PCIE-1_1") (pintype "bidirectional"))
      (node (ref "U2") (pin "TAB") (pinfunction "OUT_TAB") (pintype "output"))
    )
    (net (code "64") (name "Net-(U$4-PCIE-2)") (class "Default")
      (node (ref "C30") (pin "2") (pinfunction "2_2") (pintype "passive"))
      (node (ref "C31") (pin "2") (pinfunction "2_2") (pintype "passive"))
      (node (ref "U$4") (pin "2") (pinfunction "PCIE-2_2") (pintype "bidirectional"))
    )
    (net (code "65") (name "Net-(U$5-PCIE-1)") (class "Default")
      (node (ref "U$5") (pin "1") (pinfunction "PCIE-1_1") (pintype "bidirectional"))
      (node (ref "U7") (pin "TAB") (pinfunction "OUT_TAB") (pintype "output"))
    )
    (net (code "66") (name "Net-(U$5-PCIE-2)") (class "Default")
      (node (ref "C41") (pin "2") (pinfunction "2_2") (pintype "passive"))
      (node (ref "C44") (pin "2") (pinfunction "2_2") (pintype "passive"))
      (node (ref "U$5") (pin "2") (pinfunction "PCIE-2_2") (pintype "bidirectional"))
    )
    (net (code "67") (name "Net-(U$6-PCIE-1)") (class "Default")
      (node (ref "U$6") (pin "1") (pinfunction "PCIE-1_1") (pintype "bidirectional"))
      (node (ref "U6") (pin "TAB") (pinfunction "OUT_TAB") (pintype "output"))
    )
    (net (code "68") (name "Net-(U$6-PCIE-2)") (class "Default")
      (node (ref "C48") (pin "2") (pinfunction "2_2") (pintype "passive"))
      (node (ref "C51") (pin "2") (pinfunction "2_2") (pintype "passive"))
      (node (ref "U$6") (pin "2") (pinfunction "PCIE-2_2") (pintype "bidirectional"))
    )
    (net (code "69") (name "Net-(U$7-PCIE-2)") (class "Default")
      (node (ref "C32") (pin "2") (pinfunction "2_2") (pintype "passive"))
      (node (ref "C5") (pin "1") (pinfunction "1_1") (pintype "passive"))
      (node (ref "R27") (pin "2") (pinfunction "2_2") (pintype "passive"))
      (node (ref "SV1") (pin "2") (pinfunction "2_2") (pintype "passive"))
      (node (ref "U$7") (pin "2") (pinfunction "PCIE-2_2") (pintype "bidirectional"))
    )
    (net (code "70") (name "Net-(U$8-PCIE-1)") (class "Default")
      (node (ref "D4") (pin "A") (pinfunction "A_A") (pintype "passive"))
      (node (ref "D6") (pin "C") (pinfunction "C_C") (pintype "passive"))
      (node (ref "U$8") (pin "1") (pinfunction "PCIE-1_1") (pintype "bidirectional"))
    )
    (net (code "71") (name "Net-(U$8-PCIE-2)") (class "Default")
      (node (ref "D5") (pin "A") (pinfunction "A_A") (pintype "passive"))
      (node (ref "D7") (pin "C") (pinfunction "C_C") (pintype "passive"))
      (node (ref "U$8") (pin "2") (pinfunction "PCIE-2_2") (pintype "bidirectional"))
    )
    (net (code "72") (name "Net-(U1-HSG)") (class "Default")
      (node (ref "C26") (pin "2") (pinfunction "2_2") (pintype "passive"))
      (node (ref "D10") (pin "A") (pinfunction "A_A") (pintype "passive"))
      (node (ref "R22") (pin "1") (pinfunction "1_1") (pintype "passive"))
      (node (ref "U1") (pin "5") (pinfunction "HSG_5") (pintype "input"))
    )
    (net (code "73") (name "Net-(U1-OUT)") (class "Default")
      (node (ref "C30") (pin "1") (pinfunction "1_1") (pintype "passive"))
      (node (ref "R24") (pin "2") (pinfunction "2_2") (pintype "passive"))
      (node (ref "U1") (pin "TAB") (pinfunction "OUT_TAB") (pintype "output"))
    )
    (net (code "74") (name "Net-(U2-HSG)") (class "Default")
      (node (ref "C27") (pin "2") (pinfunction "2_2") (pintype "passive"))
      (node (ref "D11") (pin "A") (pinfunction "A_A") (pintype "passive"))
      (node (ref "R23") (pin "1") (pinfunction "1_1") (pintype "passive"))
      (node (ref "U2") (pin "5") (pinfunction "HSG_5") (pintype "input"))
    )
    (net (code "75") (name "Net-(U3-HSG)") (class "Default")
      (node (ref "C18") (pin "2") (pinfunction "2_2") (pintype "passive"))
      (node (ref "D8") (pin "A") (pinfunction "A_A") (pintype "passive"))
      (node (ref "R12") (pin "1") (pinfunction "1_1") (pintype "passive"))
      (node (ref "U3") (pin "5") (pinfunction "HSG_5") (pintype "input"))
    )
    (net (code "76") (name "Net-(U3-OUT)") (class "Default")
      (node (ref "C21") (pin "1") (pinfunction "1_1") (pintype "passive"))
      (node (ref "R19") (pin "1") (pinfunction "1_1") (pintype "passive"))
      (node (ref "U3") (pin "TAB") (pinfunction "OUT_TAB") (pintype "output"))
    )
    (net (code "77") (name "Net-(U4-HSG)") (class "Default")
      (node (ref "C20") (pin "2") (pinfunction "2_2") (pintype "passive"))
      (node (ref "D9") (pin "A") (pinfunction "A_A") (pintype "passive"))
      (node (ref "R18") (pin "1") (pinfunction "1_1") (pintype "passive"))
      (node (ref "U4") (pin "5") (pinfunction "HSG_5") (pintype "input"))
    )
    (net (code "78") (name "Net-(U5-HSG)") (class "Default")
      (node (ref "C46") (pin "2") (pinfunction "2_2") (pintype "passive"))
      (node (ref "D18") (pin "A") (pinfunction "A_A") (pintype "passive"))
      (node (ref "R35") (pin "1") (pinfunction "1_1") (pintype "passive"))
      (node (ref "U5") (pin "5") (pinfunction "HSG_5") (pintype "input"))
    )
    (net (code "79") (name "Net-(U5-OUT)") (class "Default")
      (node (ref "C48") (pin "1") (pinfunction "1_1") (pintype "passive"))
      (node (ref "R37") (pin "1") (pinfunction "1_1") (pintype "passive"))
      (node (ref "U5") (pin "TAB") (pinfunction "OUT_TAB") (pintype "output"))
    )
    (net (code "80") (name "Net-(U6-HSG)") (class "Default")
      (node (ref "C47") (pin "2") (pinfunction "2_2") (pintype "passive"))
      (node (ref "D19") (pin "A") (pinfunction "A_A") (pintype "passive"))
      (node (ref "R36") (pin "1") (pinfunction "1_1") (pintype "passive"))
      (node (ref "U6") (pin "5") (pinfunction "HSG_5") (pintype "input"))
    )
    (net (code "81") (name "Net-(U7-HSG)") (class "Default")
      (node (ref "C40") (pin "2") (pinfunction "2_2") (pintype "passive"))
      (node (ref "D17") (pin "A") (pinfunction "A_A") (pintype "passive"))
      (node (ref "R33") (pin "1") (pinfunction "1_1") (pintype "passive"))
      (node (ref "U7") (pin "5") (pinfunction "HSG_5") (pintype "input"))
    )
    (net (code "82") (name "Net-(U8-HSG)") (class "Default")
      (node (ref "C39") (pin "2") (pinfunction "2_2") (pintype "passive"))
      (node (ref "D16") (pin "A") (pinfunction "A_A") (pintype "passive"))
      (node (ref "R32") (pin "1") (pinfunction "1_1") (pintype "passive"))
      (node (ref "U8") (pin "5") (pinfunction "HSG_5") (pintype "input"))
    )
    (net (code "83") (name "Net-(U8-OUT)") (class "Default")
      (node (ref "C41") (pin "1") (pinfunction "1_1") (pintype "passive"))
      (node (ref "R34") (pin "2") (pinfunction "2_2") (pintype "passive"))
      (node (ref "U8") (pin "TAB") (pinfunction "OUT_TAB") (pintype "output"))
    )
    (net (code "84") (name "unconnected-(H1-MOUNT-PadB3,2)") (class "Default")
      (node (ref "H1") (pin "B3,2") (pinfunction "MOUNT_B3,2") (pintype "passive"))
    )
    (net (code "85") (name "unconnected-(H2-MOUNT-PadB3,2)") (class "Default")
      (node (ref "H2") (pin "B3,2") (pinfunction "MOUNT_B3,2") (pintype "passive"))
    )
    (net (code "86") (name "unconnected-(IC4C-O-Pad8)") (class "Default")
      (node (ref "IC4") (pin "8") (pinfunction "O_8") (pintype "output"))
    )
    (net (code "87") (name "unconnected-(IC5D-O-Pad11)") (class "Default")
      (node (ref "IC5") (pin "11") (pinfunction "O_11") (pintype "output"))
    )
    (net (code "88") (name "unconnected-(IC6B-~{Q}-Pad8)") (class "Default")
      (node (ref "IC6") (pin "8") (pinfunction "~{Q}_8") (pintype "output"))
    )
    (net (code "89") (name "unconnected-(IC11-N{slash}C-Pad4)") (class "Default")
      (node (ref "IC11") (pin "4") (pinfunction "N/C_4") (pintype "bidirectional"))
    )
    (net (code "90") (name "unconnected-(R29-A-Pad1)") (class "Default")
      (node (ref "R29") (pin "1") (pinfunction "A_1") (pintype "passive"))
    )
  )
)
